# Memory_V1_0.net
KiCad netlist of a schematic drawn in EAGLE
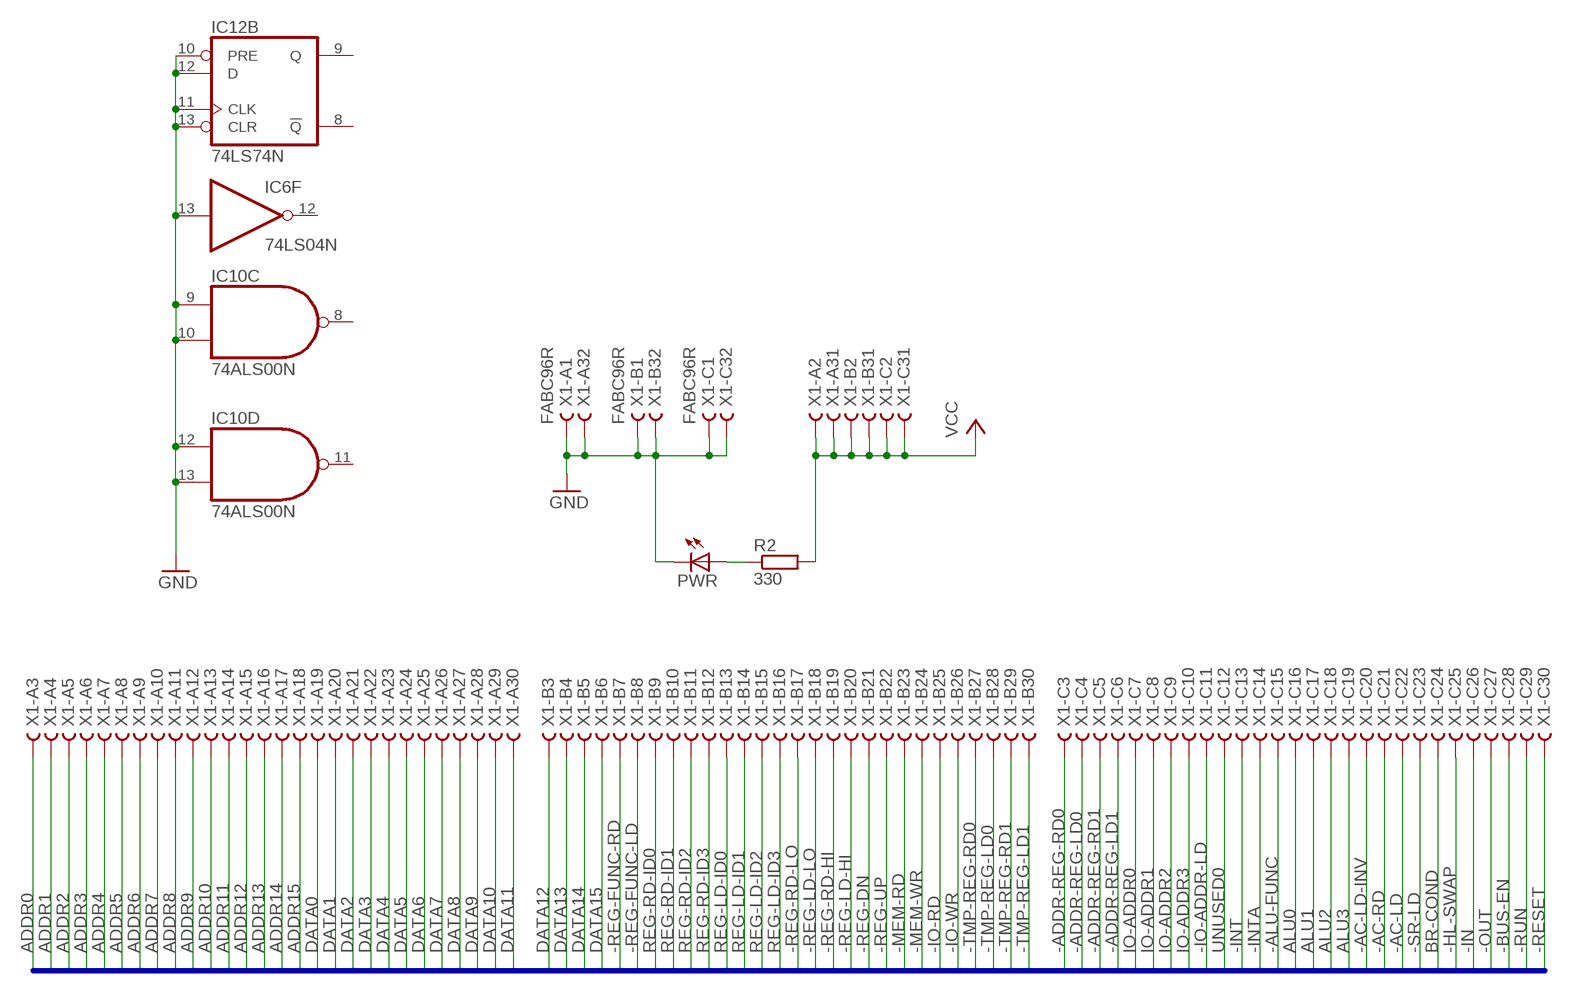
[diagram p0: schematic, sheet 1]
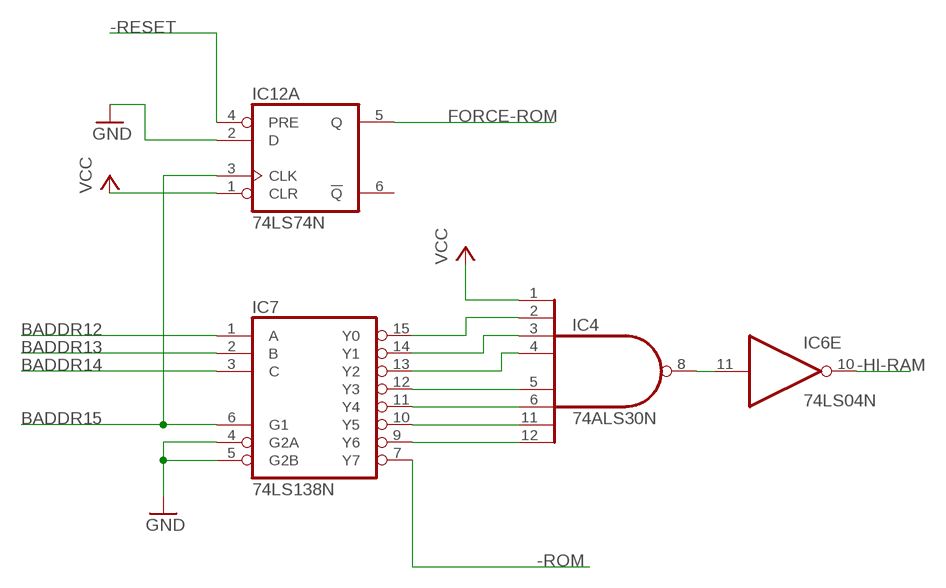
[diagram p1: schematic, sheet 2]
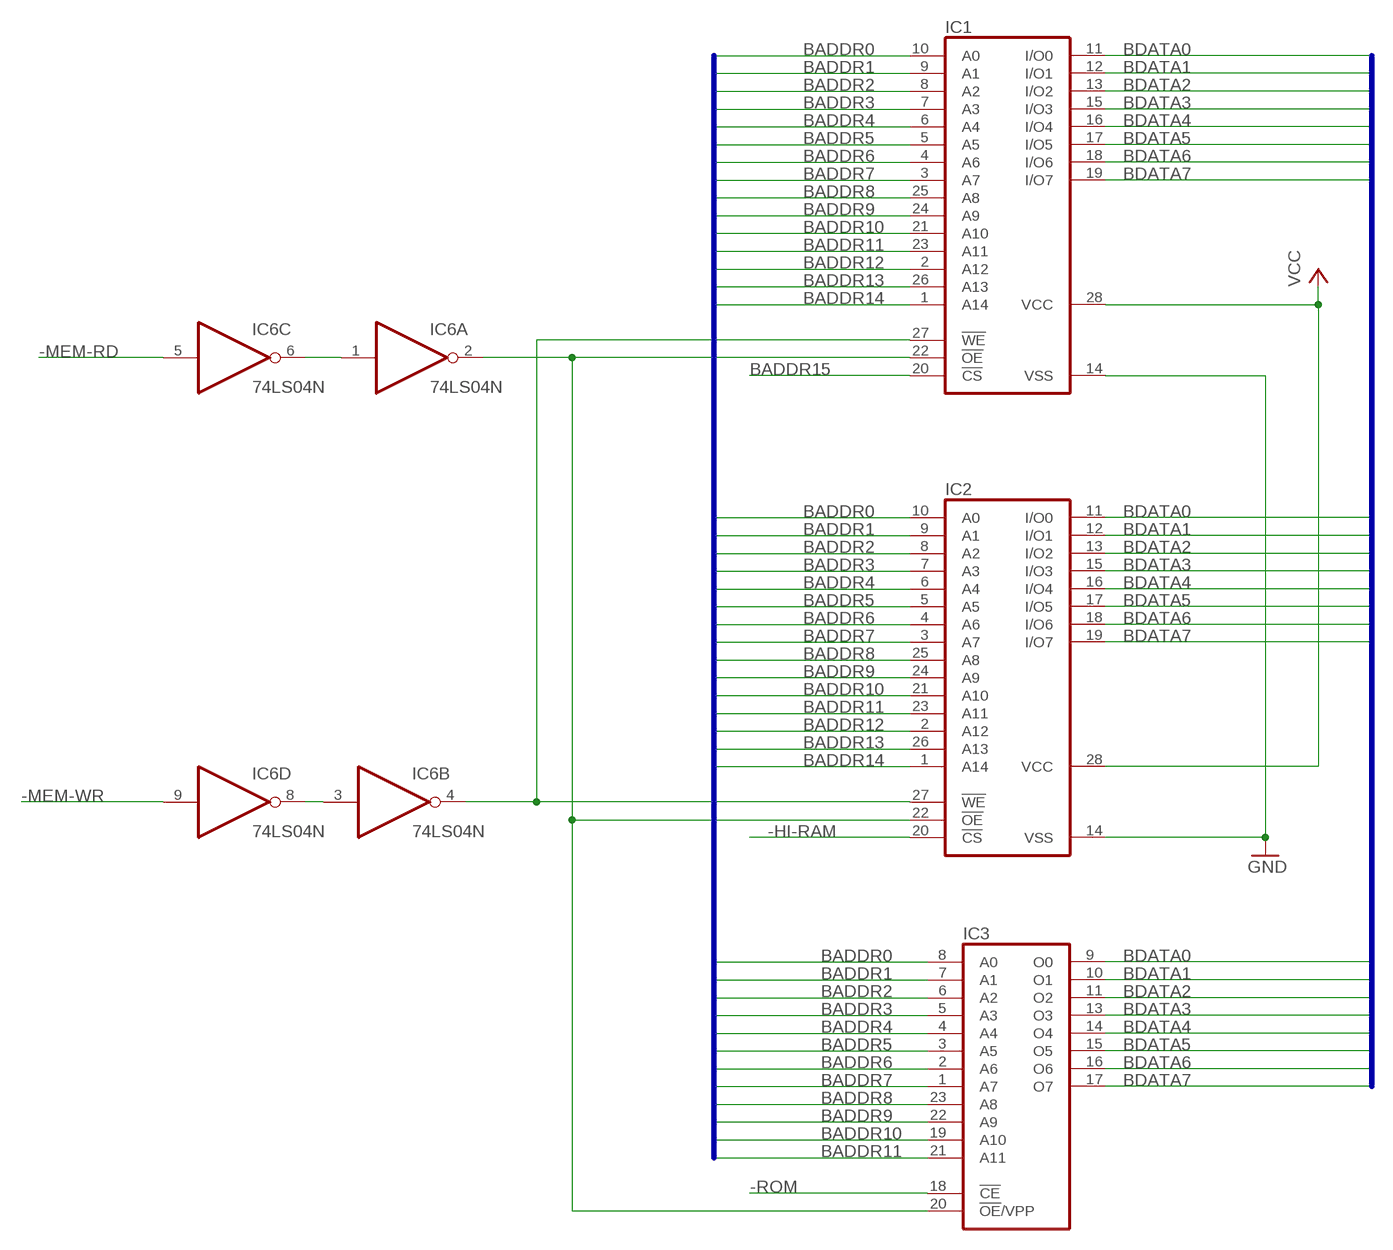
[diagram p2: schematic, sheet 3]
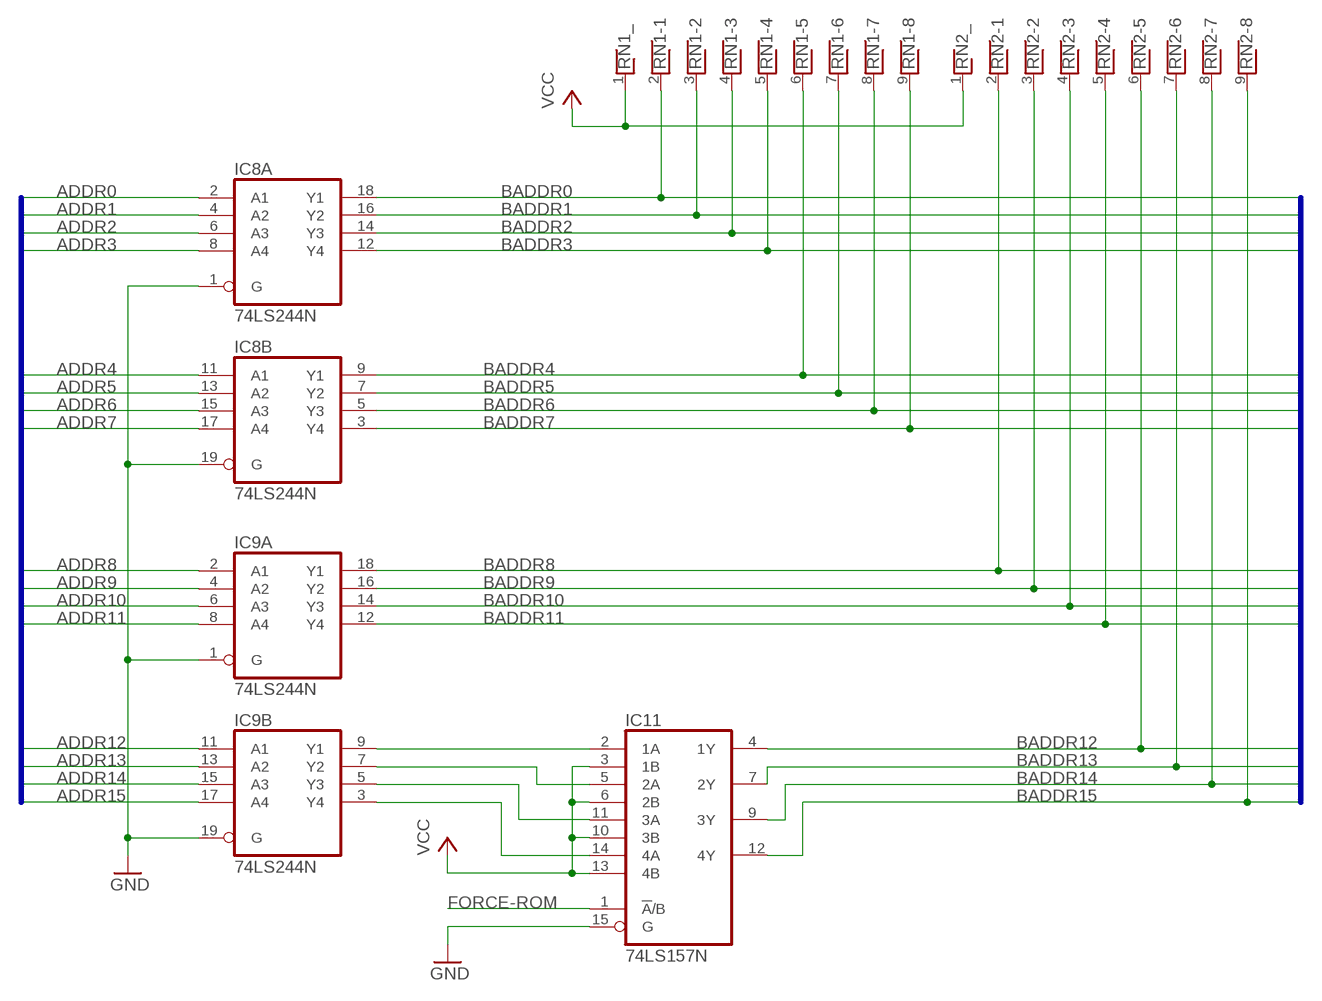
[diagram p3: schematic, sheet 4]
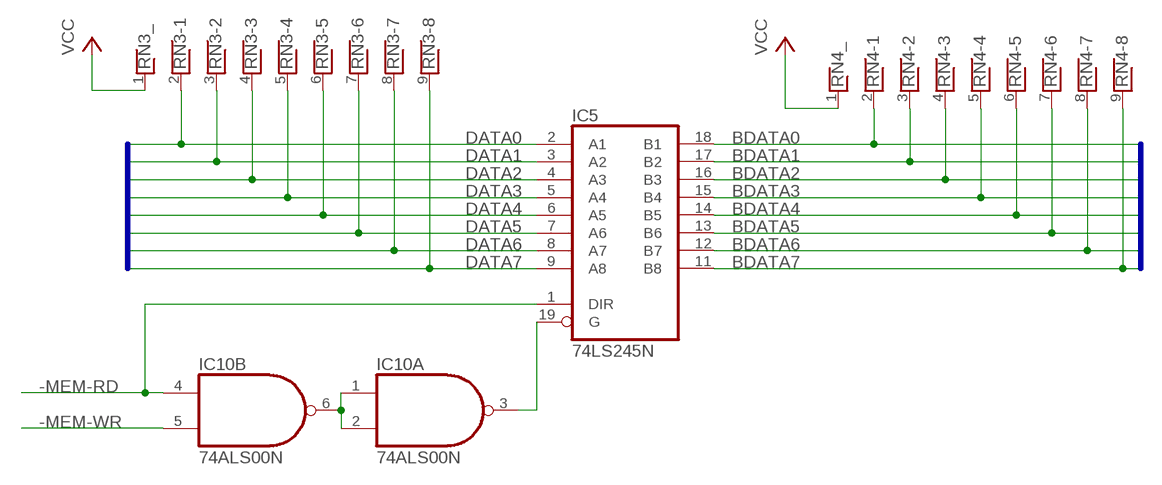
[diagram p4: schematic, sheet 5]

(export (version "E")
  (design (tool "Eeschema 10.0.6"))
  (components
    (comp (ref "IC5")
      (value "74LS245N")
      (footprint "eagle-import:DIL20")
      (libsource (lib "eagle-import") (part "74245NLS"))
    )
    (comp (ref "IC10")
      (value "74ALS00N")
      (footprint "eagle-import:DIL14")
      (libsource (lib "eagle-import") (part "7400NALS"))
    )
    (comp (ref "RN3")
      (value "RNX8")
      (footprint "eagle-import:RN-9")
      (libsource (lib "eagle-import") (part "RNX8"))
    )
    (comp (ref "RN4")
      (value "RNX8")
      (footprint "eagle-import:RN-9")
      (libsource (lib "eagle-import") (part "RNX8"))
    )
    (comp (ref "IC6")
      (value "74LS04N")
      (footprint "eagle-import:DIL14")
      (libsource (lib "eagle-import") (part "7404NLS"))
    )
    (comp (ref "IC12")
      (value "74LS74N")
      (footprint "eagle-import:DIL14")
      (libsource (lib "eagle-import") (part "7474NLS"))
    )
    (comp (ref "PWR")
      (value "LED5MM")
      (footprint "eagle-import:LED5MM")
      (libsource (lib "eagle-import") (part "LED5MM"))
    )
    (comp (ref "R2")
      (value "330")
      (footprint "eagle-import:0207_10")
      (libsource (lib "eagle-import") (part "R0207/10"))
    )
    (comp (ref "X1")
      (value "FABC96R")
      (footprint "eagle-import:FABC96R")
      (libsource (lib "eagle-import") (part "FABC96R"))
    )
    (comp (ref "IC1")
      (value "62256P")
      (footprint "eagle-import:DIL28-6")
      (libsource (lib "eagle-import") (part "62256P"))
    )
    (comp (ref "IC2")
      (value "62256P")
      (footprint "eagle-import:DIL28-6")
      (libsource (lib "eagle-import") (part "62256P"))
    )
    (comp (ref "IC3")
      (value "2732")
      (footprint "eagle-import:DIL24")
      (libsource (lib "eagle-import") (part "2732"))
    )
    (comp (ref "IC8")
      (value "74LS244N")
      (footprint "eagle-import:DIL20")
      (libsource (lib "eagle-import") (part "74xx-us_88_74244NLS"))
    )
    (comp (ref "IC9")
      (value "74LS244N")
      (footprint "eagle-import:DIL20")
      (libsource (lib "eagle-import") (part "74xx-us_88_74244NLS"))
    )
    (comp (ref "IC11")
      (value "74LS157N")
      (footprint "eagle-import:DIL16")
      (libsource (lib "eagle-import") (part "74157NLS"))
    )
    (comp (ref "RN1")
      (value "RNX8")
      (footprint "eagle-import:RN-9")
      (libsource (lib "eagle-import") (part "RNX8"))
    )
    (comp (ref "RN2")
      (value "RNX8")
      (footprint "eagle-import:RN-9")
      (libsource (lib "eagle-import") (part "RNX8"))
    )
    (comp (ref "IC4")
      (value "74ALS30N")
      (footprint "eagle-import:DIL14")
      (libsource (lib "eagle-import") (part "7430NALS"))
    )
    (comp (ref "IC7")
      (value "74LS138N")
      (footprint "eagle-import:DIL16")
      (libsource (lib "eagle-import") (part "74138NLS"))
    )
  )
  (nets
    (net (code "1") (name "-AC-LD") (class "Default")
      (node (ref "X1") (pin "C22") (pinfunction "B_C22") (pintype "passive"))
    )
    (net (code "2") (name "-AC-LD-INV") (class "Default")
      (node (ref "X1") (pin "C20") (pinfunction "B_C20") (pintype "passive"))
    )
    (net (code "3") (name "-AC-RD") (class "Default")
      (node (ref "X1") (pin "C21") (pinfunction "B_C21") (pintype "passive"))
    )
    (net (code "4") (name "-ADDR-REG-LD0") (class "Default")
      (node (ref "X1") (pin "C4") (pinfunction "B_C4") (pintype "passive"))
    )
    (net (code "5") (name "-ADDR-REG-LD1") (class "Default")
      (node (ref "X1") (pin "C6") (pinfunction "B_C6") (pintype "passive"))
    )
    (net (code "6") (name "-ADDR-REG-RD0") (class "Default")
      (node (ref "X1") (pin "C3") (pinfunction "B_C3") (pintype "passive"))
    )
    (net (code "7") (name "-ADDR-REG-RD1") (class "Default")
      (node (ref "X1") (pin "C5") (pinfunction "B_C5") (pintype "passive"))
    )
    (net (code "8") (name "-ALU-FUNC") (class "Default")
      (node (ref "X1") (pin "C15") (pinfunction "B_C15") (pintype "passive"))
    )
    (net (code "9") (name "-BUS-EN") (class "Default")
      (node (ref "X1") (pin "C28") (pinfunction "B_C28") (pintype "passive"))
    )
    (net (code "10") (name "-HI-RAM") (class "Default")
      (node (ref "IC2") (pin "20") (pinfunction "~{CS}_20") (pintype "input"))
      (node (ref "IC6") (pin "10") (pinfunction "O_10") (pintype "output"))
    )
    (net (code "11") (name "-HL-SWAP") (class "Default")
      (node (ref "X1") (pin "C25") (pinfunction "B_C25") (pintype "passive"))
    )
    (net (code "12") (name "-IN") (class "Default")
      (node (ref "X1") (pin "C26") (pinfunction "B_C26") (pintype "passive"))
    )
    (net (code "13") (name "-INT") (class "Default")
      (node (ref "X1") (pin "C13") (pinfunction "B_C13") (pintype "passive"))
    )
    (net (code "14") (name "-INTA") (class "Default")
      (node (ref "X1") (pin "C14") (pinfunction "B_C14") (pintype "passive"))
    )
    (net (code "15") (name "-IO-ADDR-LD") (class "Default")
      (node (ref "X1") (pin "C11") (pinfunction "B_C11") (pintype "passive"))
    )
    (net (code "16") (name "-IO-RD") (class "Default")
      (node (ref "X1") (pin "B25") (pinfunction "B_B25") (pintype "passive"))
    )
    (net (code "17") (name "-IO-WR") (class "Default")
      (node (ref "X1") (pin "B26") (pinfunction "B_B26") (pintype "passive"))
    )
    (net (code "18") (name "-MEM-RD") (class "Default")
      (node (ref "IC10") (pin "4") (pinfunction "I0_4") (pintype "input"))
      (node (ref "IC5") (pin "1") (pinfunction "DIR_1") (pintype "input"))
      (node (ref "IC6") (pin "5") (pinfunction "I_5") (pintype "input"))
      (node (ref "X1") (pin "B23") (pinfunction "B_B23") (pintype "passive"))
    )
    (net (code "19") (name "-MEM-WR") (class "Default")
      (node (ref "IC10") (pin "5") (pinfunction "I1_5") (pintype "input"))
      (node (ref "IC6") (pin "9") (pinfunction "I_9") (pintype "input"))
      (node (ref "X1") (pin "B24") (pinfunction "B_B24") (pintype "passive"))
    )
    (net (code "20") (name "-OUT") (class "Default")
      (node (ref "X1") (pin "C27") (pinfunction "B_C27") (pintype "passive"))
    )
    (net (code "21") (name "-REG-DN") (class "Default")
      (node (ref "X1") (pin "B21") (pinfunction "B_B21") (pintype "passive"))
    )
    (net (code "22") (name "-REG-FUNC-LD") (class "Default")
      (node (ref "X1") (pin "B8") (pinfunction "B_B8") (pintype "passive"))
    )
    (net (code "23") (name "-REG-FUNC-RD") (class "Default")
      (node (ref "X1") (pin "B7") (pinfunction "B_B7") (pintype "passive"))
    )
    (net (code "24") (name "-REG-LD-HI") (class "Default")
      (node (ref "X1") (pin "B20") (pinfunction "B_B20") (pintype "passive"))
    )
    (net (code "25") (name "-REG-LD-LO") (class "Default")
      (node (ref "X1") (pin "B18") (pinfunction "B_B18") (pintype "passive"))
    )
    (net (code "26") (name "-REG-RD-HI") (class "Default")
      (node (ref "X1") (pin "B19") (pinfunction "B_B19") (pintype "passive"))
    )
    (net (code "27") (name "-REG-RD-LO") (class "Default")
      (node (ref "X1") (pin "B17") (pinfunction "B_B17") (pintype "passive"))
    )
    (net (code "28") (name "-REG-UP") (class "Default")
      (node (ref "X1") (pin "B22") (pinfunction "B_B22") (pintype "passive"))
    )
    (net (code "29") (name "-RESET") (class "Default")
      (node (ref "IC12") (pin "4") (pinfunction "PRE_4") (pintype "input"))
      (node (ref "X1") (pin "C30") (pinfunction "B_C30") (pintype "passive"))
    )
    (net (code "30") (name "-ROM") (class "Default")
      (node (ref "IC3") (pin "18") (pinfunction "~{CE}_18") (pintype "input"))
      (node (ref "IC7") (pin "7") (pinfunction "Y7_7") (pintype "output"))
    )
    (net (code "31") (name "-RUN") (class "Default")
      (node (ref "X1") (pin "C29") (pinfunction "B_C29") (pintype "passive"))
    )
    (net (code "32") (name "-SR-LD") (class "Default")
      (node (ref "X1") (pin "C23") (pinfunction "B_C23") (pintype "passive"))
    )
    (net (code "33") (name "-TMP-REG-LD0") (class "Default")
      (node (ref "X1") (pin "B28") (pinfunction "B_B28") (pintype "passive"))
    )
    (net (code "34") (name "-TMP-REG-LD1") (class "Default")
      (node (ref "X1") (pin "B30") (pinfunction "B_B30") (pintype "passive"))
    )
    (net (code "35") (name "-TMP-REG-RD0") (class "Default")
      (node (ref "X1") (pin "B27") (pinfunction "B_B27") (pintype "passive"))
    )
    (net (code "36") (name "-TMP-REG-RD1") (class "Default")
      (node (ref "X1") (pin "B29") (pinfunction "B_B29") (pintype "passive"))
    )
    (net (code "37") (name "ADDR0") (class "Default")
      (node (ref "IC8") (pin "2") (pinfunction "A1_2") (pintype "input"))
      (node (ref "X1") (pin "A3") (pinfunction "B_A3") (pintype "passive"))
    )
    (net (code "38") (name "ADDR1") (class "Default")
      (node (ref "IC8") (pin "4") (pinfunction "A2_4") (pintype "input"))
      (node (ref "X1") (pin "A4") (pinfunction "B_A4") (pintype "passive"))
    )
    (net (code "39") (name "ADDR2") (class "Default")
      (node (ref "IC8") (pin "6") (pinfunction "A3_6") (pintype "input"))
      (node (ref "X1") (pin "A5") (pinfunction "B_A5") (pintype "passive"))
    )
    (net (code "40") (name "ADDR3") (class "Default")
      (node (ref "IC8") (pin "8") (pinfunction "A4_8") (pintype "input"))
      (node (ref "X1") (pin "A6") (pinfunction "B_A6") (pintype "passive"))
    )
    (net (code "41") (name "ADDR4") (class "Default")
      (node (ref "IC8") (pin "11") (pinfunction "A1_11") (pintype "input"))
      (node (ref "X1") (pin "A7") (pinfunction "B_A7") (pintype "passive"))
    )
    (net (code "42") (name "ADDR5") (class "Default")
      (node (ref "IC8") (pin "13") (pinfunction "A2_13") (pintype "input"))
      (node (ref "X1") (pin "A8") (pinfunction "B_A8") (pintype "passive"))
    )
    (net (code "43") (name "ADDR6") (class "Default")
      (node (ref "IC8") (pin "15") (pinfunction "A3_15") (pintype "input"))
      (node (ref "X1") (pin "A9") (pinfunction "B_A9") (pintype "passive"))
    )
    (net (code "44") (name "ADDR7") (class "Default")
      (node (ref "IC8") (pin "17") (pinfunction "A4_17") (pintype "input"))
      (node (ref "X1") (pin "A10") (pinfunction "B_A10") (pintype "passive"))
    )
    (net (code "45") (name "ADDR8") (class "Default")
      (node (ref "IC9") (pin "2") (pinfunction "A1_2") (pintype "input"))
      (node (ref "X1") (pin "A11") (pinfunction "B_A11") (pintype "passive"))
    )
    (net (code "46") (name "ADDR9") (class "Default")
      (node (ref "IC9") (pin "4") (pinfunction "A2_4") (pintype "input"))
      (node (ref "X1") (pin "A12") (pinfunction "B_A12") (pintype "passive"))
    )
    (net (code "47") (name "ADDR10") (class "Default")
      (node (ref "IC9") (pin "6") (pinfunction "A3_6") (pintype "input"))
      (node (ref "X1") (pin "A13") (pinfunction "B_A13") (pintype "passive"))
    )
    (net (code "48") (name "ADDR11") (class "Default")
      (node (ref "IC9") (pin "8") (pinfunction "A4_8") (pintype "input"))
      (node (ref "X1") (pin "A14") (pinfunction "B_A14") (pintype "passive"))
    )
    (net (code "49") (name "ADDR12") (class "Default")
      (node (ref "IC9") (pin "11") (pinfunction "A1_11") (pintype "input"))
      (node (ref "X1") (pin "A15") (pinfunction "B_A15") (pintype "passive"))
    )
    (net (code "50") (name "ADDR13") (class "Default")
      (node (ref "IC9") (pin "13") (pinfunction "A2_13") (pintype "input"))
      (node (ref "X1") (pin "A16") (pinfunction "B_A16") (pintype "passive"))
    )
    (net (code "51") (name "ADDR14") (class "Default")
      (node (ref "IC9") (pin "15") (pinfunction "A3_15") (pintype "input"))
      (node (ref "X1") (pin "A17") (pinfunction "B_A17") (pintype "passive"))
    )
    (net (code "52") (name "ADDR15") (class "Default")
      (node (ref "IC9") (pin "17") (pinfunction "A4_17") (pintype "input"))
      (node (ref "X1") (pin "A18") (pinfunction "B_A18") (pintype "passive"))
    )
    (net (code "53") (name "ALU0") (class "Default")
      (node (ref "X1") (pin "C16") (pinfunction "B_C16") (pintype "passive"))
    )
    (net (code "54") (name "ALU1") (class "Default")
      (node (ref "X1") (pin "C17") (pinfunction "B_C17") (pintype "passive"))
    )
    (net (code "55") (name "ALU2") (class "Default")
      (node (ref "X1") (pin "C18") (pinfunction "B_C18") (pintype "passive"))
    )
    (net (code "56") (name "ALU3") (class "Default")
      (node (ref "X1") (pin "C19") (pinfunction "B_C19") (pintype "passive"))
    )
    (net (code "57") (name "BADDR0") (class "Default")
      (node (ref "IC1") (pin "10") (pinfunction "A0_10") (pintype "input"))
      (node (ref "IC2") (pin "10") (pinfunction "A0_10") (pintype "input"))
      (node (ref "IC3") (pin "8") (pinfunction "A0_8") (pintype "input"))
      (node (ref "IC8") (pin "18") (pinfunction "Y1_18") (pintype "tri_state"))
      (node (ref "RN1") (pin "2") (pinfunction "1_2") (pintype "passive"))
    )
    (net (code "58") (name "BADDR1") (class "Default")
      (node (ref "IC1") (pin "9") (pinfunction "A1_9") (pintype "input"))
      (node (ref "IC2") (pin "9") (pinfunction "A1_9") (pintype "input"))
      (node (ref "IC3") (pin "7") (pinfunction "A1_7") (pintype "input"))
      (node (ref "IC8") (pin "16") (pinfunction "Y2_16") (pintype "tri_state"))
      (node (ref "RN1") (pin "3") (pinfunction "1_3") (pintype "passive"))
    )
    (net (code "59") (name "BADDR2") (class "Default")
      (node (ref "IC1") (pin "8") (pinfunction "A2_8") (pintype "input"))
      (node (ref "IC2") (pin "8") (pinfunction "A2_8") (pintype "input"))
      (node (ref "IC3") (pin "6") (pinfunction "A2_6") (pintype "input"))
      (node (ref "IC8") (pin "14") (pinfunction "Y3_14") (pintype "tri_state"))
      (node (ref "RN1") (pin "4") (pinfunction "1_4") (pintype "passive"))
    )
    (net (code "60") (name "BADDR3") (class "Default")
      (node (ref "IC1") (pin "7") (pinfunction "A3_7") (pintype "input"))
      (node (ref "IC2") (pin "7") (pinfunction "A3_7") (pintype "input"))
      (node (ref "IC3") (pin "5") (pinfunction "A3_5") (pintype "input"))
      (node (ref "IC8") (pin "12") (pinfunction "Y4_12") (pintype "tri_state"))
      (node (ref "RN1") (pin "5") (pinfunction "1_5") (pintype "passive"))
    )
    (net (code "61") (name "BADDR4") (class "Default")
      (node (ref "IC1") (pin "6") (pinfunction "A4_6") (pintype "input"))
      (node (ref "IC2") (pin "6") (pinfunction "A4_6") (pintype "input"))
      (node (ref "IC3") (pin "4") (pinfunction "A4_4") (pintype "input"))
      (node (ref "IC8") (pin "9") (pinfunction "Y1_9") (pintype "tri_state"))
      (node (ref "RN1") (pin "6") (pinfunction "1_6") (pintype "passive"))
    )
    (net (code "62") (name "BADDR5") (class "Default")
      (node (ref "IC1") (pin "5") (pinfunction "A5_5") (pintype "input"))
      (node (ref "IC2") (pin "5") (pinfunction "A5_5") (pintype "input"))
      (node (ref "IC3") (pin "3") (pinfunction "A5_3") (pintype "input"))
      (node (ref "IC8") (pin "7") (pinfunction "Y2_7") (pintype "tri_state"))
      (node (ref "RN1") (pin "7") (pinfunction "1_7") (pintype "passive"))
    )
    (net (code "63") (name "BADDR6") (class "Default")
      (node (ref "IC1") (pin "4") (pinfunction "A6_4") (pintype "input"))
      (node (ref "IC2") (pin "4") (pinfunction "A6_4") (pintype "input"))
      (node (ref "IC3") (pin "2") (pinfunction "A6_2") (pintype "input"))
      (node (ref "IC8") (pin "5") (pinfunction "Y3_5") (pintype "tri_state"))
      (node (ref "RN1") (pin "8") (pinfunction "1_8") (pintype "passive"))
    )
    (net (code "64") (name "BADDR7") (class "Default")
      (node (ref "IC1") (pin "3") (pinfunction "A7_3") (pintype "input"))
      (node (ref "IC2") (pin "3") (pinfunction "A7_3") (pintype "input"))
      (node (ref "IC3") (pin "1") (pinfunction "A7_1") (pintype "input"))
      (node (ref "IC8") (pin "3") (pinfunction "Y4_3") (pintype "tri_state"))
      (node (ref "RN1") (pin "9") (pinfunction "1_9") (pintype "passive"))
    )
    (net (code "65") (name "BADDR8") (class "Default")
      (node (ref "IC1") (pin "25") (pinfunction "A8_25") (pintype "input"))
      (node (ref "IC2") (pin "25") (pinfunction "A8_25") (pintype "input"))
      (node (ref "IC3") (pin "23") (pinfunction "A8_23") (pintype "input"))
      (node (ref "IC9") (pin "18") (pinfunction "Y1_18") (pintype "tri_state"))
      (node (ref "RN2") (pin "2") (pinfunction "1_2") (pintype "passive"))
    )
    (net (code "66") (name "BADDR9") (class "Default")
      (node (ref "IC1") (pin "24") (pinfunction "A9_24") (pintype "input"))
      (node (ref "IC2") (pin "24") (pinfunction "A9_24") (pintype "input"))
      (node (ref "IC3") (pin "22") (pinfunction "A9_22") (pintype "input"))
      (node (ref "IC9") (pin "16") (pinfunction "Y2_16") (pintype "tri_state"))
      (node (ref "RN2") (pin "3") (pinfunction "1_3") (pintype "passive"))
    )
    (net (code "67") (name "BADDR10") (class "Default")
      (node (ref "IC1") (pin "21") (pinfunction "A10_21") (pintype "input"))
      (node (ref "IC2") (pin "21") (pinfunction "A10_21") (pintype "input"))
      (node (ref "IC3") (pin "19") (pinfunction "A10_19") (pintype "input"))
      (node (ref "IC9") (pin "14") (pinfunction "Y3_14") (pintype "tri_state"))
      (node (ref "RN2") (pin "4") (pinfunction "1_4") (pintype "passive"))
    )
    (net (code "68") (name "BADDR11") (class "Default")
      (node (ref "IC1") (pin "23") (pinfunction "A11_23") (pintype "input"))
      (node (ref "IC2") (pin "23") (pinfunction "A11_23") (pintype "input"))
      (node (ref "IC3") (pin "21") (pinfunction "A11_21") (pintype "input"))
      (node (ref "IC9") (pin "12") (pinfunction "Y4_12") (pintype "tri_state"))
      (node (ref "RN2") (pin "5") (pinfunction "1_5") (pintype "passive"))
    )
    (net (code "69") (name "BADDR12") (class "Default")
      (node (ref "IC1") (pin "2") (pinfunction "A12_2") (pintype "input"))
      (node (ref "IC11") (pin "4") (pinfunction "1Y_4") (pintype "output"))
      (node (ref "IC2") (pin "2") (pinfunction "A12_2") (pintype "input"))
      (node (ref "IC7") (pin "1") (pinfunction "A_1") (pintype "input"))
      (node (ref "RN2") (pin "6") (pinfunction "1_6") (pintype "passive"))
    )
    (net (code "70") (name "BADDR13") (class "Default")
      (node (ref "IC1") (pin "26") (pinfunction "A13_26") (pintype "input"))
      (node (ref "IC11") (pin "7") (pinfunction "2Y_7") (pintype "output"))
      (node (ref "IC2") (pin "26") (pinfunction "A13_26") (pintype "input"))
      (node (ref "IC7") (pin "2") (pinfunction "B_2") (pintype "input"))
      (node (ref "RN2") (pin "7") (pinfunction "1_7") (pintype "passive"))
    )
    (net (code "71") (name "BADDR14") (class "Default")
      (node (ref "IC1") (pin "1") (pinfunction "A14_1") (pintype "input"))
      (node (ref "IC11") (pin "9") (pinfunction "3Y_9") (pintype "output"))
      (node (ref "IC2") (pin "1") (pinfunction "A14_1") (pintype "input"))
      (node (ref "IC7") (pin "3") (pinfunction "C_3") (pintype "input"))
      (node (ref "RN2") (pin "8") (pinfunction "1_8") (pintype "passive"))
    )
    (net (code "72") (name "BADDR15") (class "Default")
      (node (ref "IC1") (pin "20") (pinfunction "~{CS}_20") (pintype "input"))
      (node (ref "IC11") (pin "12") (pinfunction "4Y_12") (pintype "output"))
      (node (ref "IC12") (pin "3") (pinfunction "CLK_3") (pintype "input"))
      (node (ref "IC7") (pin "6") (pinfunction "G1_6") (pintype "input"))
      (node (ref "RN2") (pin "9") (pinfunction "1_9") (pintype "passive"))
    )
    (net (code "73") (name "BDATA0") (class "Default")
      (node (ref "IC1") (pin "11") (pinfunction "I/O0_11") (pintype "bidirectional"))
      (node (ref "IC2") (pin "11") (pinfunction "I/O0_11") (pintype "bidirectional"))
      (node (ref "IC3") (pin "9") (pinfunction "O0_9") (pintype "tri_state"))
      (node (ref "IC5") (pin "18") (pinfunction "B1_18") (pintype "bidirectional"))
      (node (ref "RN4") (pin "2") (pinfunction "1_2") (pintype "passive"))
    )
    (net (code "74") (name "BDATA1") (class "Default")
      (node (ref "IC1") (pin "12") (pinfunction "I/O1_12") (pintype "bidirectional"))
      (node (ref "IC2") (pin "12") (pinfunction "I/O1_12") (pintype "bidirectional"))
      (node (ref "IC3") (pin "10") (pinfunction "O1_10") (pintype "tri_state"))
      (node (ref "IC5") (pin "17") (pinfunction "B2_17") (pintype "bidirectional"))
      (node (ref "RN4") (pin "3") (pinfunction "1_3") (pintype "passive"))
    )
    (net (code "75") (name "BDATA2") (class "Default")
      (node (ref "IC1") (pin "13") (pinfunction "I/O2_13") (pintype "bidirectional"))
      (node (ref "IC2") (pin "13") (pinfunction "I/O2_13") (pintype "bidirectional"))
      (node (ref "IC3") (pin "11") (pinfunction "O2_11") (pintype "tri_state"))
      (node (ref "IC5") (pin "16") (pinfunction "B3_16") (pintype "bidirectional"))
      (node (ref "RN4") (pin "4") (pinfunction "1_4") (pintype "passive"))
    )
    (net (code "76") (name "BDATA3") (class "Default")
      (node (ref "IC1") (pin "15") (pinfunction "I/O3_15") (pintype "bidirectional"))
      (node (ref "IC2") (pin "15") (pinfunction "I/O3_15") (pintype "bidirectional"))
      (node (ref "IC3") (pin "13") (pinfunction "O3_13") (pintype "tri_state"))
      (node (ref "IC5") (pin "15") (pinfunction "B4_15") (pintype "bidirectional"))
      (node (ref "RN4") (pin "5") (pinfunction "1_5") (pintype "passive"))
    )
    (net (code "77") (name "BDATA4") (class "Default")
      (node (ref "IC1") (pin "16") (pinfunction "I/O4_16") (pintype "bidirectional"))
      (node (ref "IC2") (pin "16") (pinfunction "I/O4_16") (pintype "bidirectional"))
      (node (ref "IC3") (pin "14") (pinfunction "O4_14") (pintype "tri_state"))
      (node (ref "IC5") (pin "14") (pinfunction "B5_14") (pintype "bidirectional"))
      (node (ref "RN4") (pin "6") (pinfunction "1_6") (pintype "passive"))
    )
    (net (code "78") (name "BDATA5") (class "Default")
      (node (ref "IC1") (pin "17") (pinfunction "I/O5_17") (pintype "bidirectional"))
      (node (ref "IC2") (pin "17") (pinfunction "I/O5_17") (pintype "bidirectional"))
      (node (ref "IC3") (pin "15") (pinfunction "O5_15") (pintype "tri_state"))
      (node (ref "IC5") (pin "13") (pinfunction "B6_13") (pintype "bidirectional"))
      (node (ref "RN4") (pin "7") (pinfunction "1_7") (pintype "passive"))
    )
    (net (code "79") (name "BDATA6") (class "Default")
      (node (ref "IC1") (pin "18") (pinfunction "I/O6_18") (pintype "bidirectional"))
      (node (ref "IC2") (pin "18") (pinfunction "I/O6_18") (pintype "bidirectional"))
      (node (ref "IC3") (pin "16") (pinfunction "O6_16") (pintype "tri_state"))
      (node (ref "IC5") (pin "12") (pinfunction "B7_12") (pintype "bidirectional"))
      (node (ref "RN4") (pin "8") (pinfunction "1_8") (pintype "passive"))
    )
    (net (code "80") (name "BDATA7") (class "Default")
      (node (ref "IC1") (pin "19") (pinfunction "I/O7_19") (pintype "bidirectional"))
      (node (ref "IC2") (pin "19") (pinfunction "I/O7_19") (pintype "bidirectional"))
      (node (ref "IC3") (pin "17") (pinfunction "O7_17") (pintype "tri_state"))
      (node (ref "IC5") (pin "11") (pinfunction "B8_11") (pintype "bidirectional"))
      (node (ref "RN4") (pin "9") (pinfunction "1_9") (pintype "passive"))
    )
    (net (code "81") (name "BR-COND") (class "Default")
      (node (ref "X1") (pin "C24") (pinfunction "B_C24") (pintype "passive"))
    )
    (net (code "82") (name "DATA0") (class "Default")
      (node (ref "IC5") (pin "2") (pinfunction "A1_2") (pintype "bidirectional"))
      (node (ref "RN3") (pin "2") (pinfunction "1_2") (pintype "passive"))
      (node (ref "X1") (pin "A19") (pinfunction "B_A19") (pintype "passive"))
    )
    (net (code "83") (name "DATA1") (class "Default")
      (node (ref "IC5") (pin "3") (pinfunction "A2_3") (pintype "bidirectional"))
      (node (ref "RN3") (pin "3") (pinfunction "1_3") (pintype "passive"))
      (node (ref "X1") (pin "A20") (pinfunction "B_A20") (pintype "passive"))
    )
    (net (code "84") (name "DATA2") (class "Default")
      (node (ref "IC5") (pin "4") (pinfunction "A3_4") (pintype "bidirectional"))
      (node (ref "RN3") (pin "4") (pinfunction "1_4") (pintype "passive"))
      (node (ref "X1") (pin "A21") (pinfunction "B_A21") (pintype "passive"))
    )
    (net (code "85") (name "DATA3") (class "Default")
      (node (ref "IC5") (pin "5") (pinfunction "A4_5") (pintype "bidirectional"))
      (node (ref "RN3") (pin "5") (pinfunction "1_5") (pintype "passive"))
      (node (ref "X1") (pin "A22") (pinfunction "B_A22") (pintype "passive"))
    )
    (net (code "86") (name "DATA4") (class "Default")
      (node (ref "IC5") (pin "6") (pinfunction "A5_6") (pintype "bidirectional"))
      (node (ref "RN3") (pin "6") (pinfunction "1_6") (pintype "passive"))
      (node (ref "X1") (pin "A23") (pinfunction "B_A23") (pintype "passive"))
    )
    (net (code "87") (name "DATA5") (class "Default")
      (node (ref "IC5") (pin "7") (pinfunction "A6_7") (pintype "bidirectional"))
      (node (ref "RN3") (pin "7") (pinfunction "1_7") (pintype "passive"))
      (node (ref "X1") (pin "A24") (pinfunction "B_A24") (pintype "passive"))
    )
    (net (code "88") (name "DATA6") (class "Default")
      (node (ref "IC5") (pin "8") (pinfunction "A7_8") (pintype "bidirectional"))
      (node (ref "RN3") (pin "8") (pinfunction "1_8") (pintype "passive"))
      (node (ref "X1") (pin "A25") (pinfunction "B_A25") (pintype "passive"))
    )
    (net (code "89") (name "DATA7") (class "Default")
      (node (ref "IC5") (pin "9") (pinfunction "A8_9") (pintype "bidirectional"))
      (node (ref "RN3") (pin "9") (pinfunction "1_9") (pintype "passive"))
      (node (ref "X1") (pin "A26") (pinfunction "B_A26") (pintype "passive"))
    )
    (net (code "90") (name "DATA8") (class "Default")
      (node (ref "X1") (pin "A27") (pinfunction "B_A27") (pintype "passive"))
    )
    (net (code "91") (name "DATA9") (class "Default")
      (node (ref "X1") (pin "A28") (pinfunction "B_A28") (pintype "passive"))
    )
    (net (code "92") (name "DATA10") (class "Default")
      (node (ref "X1") (pin "A29") (pinfunction "B_A29") (pintype "passive"))
    )
    (net (code "93") (name "DATA11") (class "Default")
      (node (ref "X1") (pin "A30") (pinfunction "B_A30") (pintype "passive"))
    )
    (net (code "94") (name "DATA12") (class "Default")
      (node (ref "X1") (pin "B3") (pinfunction "B_B3") (pintype "passive"))
    )
    (net (code "95") (name "DATA13") (class "Default")
      (node (ref "X1") (pin "B4") (pinfunction "B_B4") (pintype "passive"))
    )
    (net (code "96") (name "DATA14") (class "Default")
      (node (ref "X1") (pin "B5") (pinfunction "B_B5") (pintype "passive"))
    )
    (net (code "97") (name "DATA15") (class "Default")
      (node (ref "X1") (pin "B6") (pinfunction "B_B6") (pintype "passive"))
    )
    (net (code "98") (name "FORCE-ROM") (class "Default")
      (node (ref "IC11") (pin "1") (pinfunction "~{A}/B_1") (pintype "input"))
      (node (ref "IC12") (pin "5") (pinfunction "Q_5") (pintype "output"))
    )
    (net (code "99") (name "GND") (class "Default")
      (node (ref "IC1") (pin "14") (pinfunction "VSS_14") (pintype "power_in"))
      (node (ref "IC10") (pin "10") (pinfunction "I1_10") (pintype "input"))
      (node (ref "IC10") (pin "12") (pinfunction "I0_12") (pintype "input"))
      (node (ref "IC10") (pin "13") (pinfunction "I1_13") (pintype "input"))
      (node (ref "IC10") (pin "9") (pinfunction "I0_9") (pintype "input"))
      (node (ref "IC11") (pin "15") (pinfunction "G_15") (pintype "input"))
      (node (ref "IC12") (pin "10") (pinfunction "PRE_10") (pintype "input"))
      (node (ref "IC12") (pin "11") (pinfunction "CLK_11") (pintype "input"))
      (node (ref "IC12") (pin "12") (pinfunction "D_12") (pintype "input"))
      (node (ref "IC12") (pin "13") (pinfunction "CLR_13") (pintype "input"))
      (node (ref "IC12") (pin "2") (pinfunction "D_2") (pintype "input"))
      (node (ref "IC2") (pin "14") (pinfunction "VSS_14") (pintype "power_in"))
      (node (ref "IC6") (pin "13") (pinfunction "I_13") (pintype "input"))
      (node (ref "IC7") (pin "4") (pinfunction "G2A_4") (pintype "input"))
      (node (ref "IC7") (pin "5") (pinfunction "G2B_5") (pintype "input"))
      (node (ref "IC8") (pin "1") (pinfunction "G_1") (pintype "input"))
      (node (ref "IC8") (pin "19") (pinfunction "G_19") (pintype "input"))
      (node (ref "IC9") (pin "1") (pinfunction "G_1") (pintype "input"))
      (node (ref "IC9") (pin "19") (pinfunction "G_19") (pintype "input"))
      (node (ref "PWR") (pin "K") (pinfunction "C_K") (pintype "passive"))
      (node (ref "X1") (pin "A1") (pinfunction "B_A1") (pintype "passive"))
      (node (ref "X1") (pin "A32") (pinfunction "B_A32") (pintype "passive"))
      (node (ref "X1") (pin "B1") (pinfunction "B_B1") (pintype "passive"))
      (node (ref "X1") (pin "B32") (pinfunction "B_B32") (pintype "passive"))
      (node (ref "X1") (pin "C1") (pinfunction "B_C1") (pintype "passive"))
      (node (ref "X1") (pin "C32") (pinfunction "B_C32") (pintype "passive"))
    )
    (net (code "100") (name "IO-ADDR0") (class "Default")
      (node (ref "X1") (pin "C7") (pinfunction "B_C7") (pintype "passive"))
    )
    (net (code "101") (name "IO-ADDR1") (class "Default")
      (node (ref "X1") (pin "C8") (pinfunction "B_C8") (pintype "passive"))
    )
    (net (code "102") (name "IO-ADDR2") (class "Default")
      (node (ref "X1") (pin "C9") (pinfunction "B_C9") (pintype "passive"))
    )
    (net (code "103") (name "IO-ADDR3") (class "Default")
      (node (ref "X1") (pin "C10") (pinfunction "B_C10") (pintype "passive"))
    )
    (net (code "104") (name "Net-(IC1-~{OE})") (class "Default")
      (node (ref "IC1") (pin "22") (pinfunction "~{OE}_22") (pintype "input"))
      (node (ref "IC2") (pin "22") (pinfunction "~{OE}_22") (pintype "input"))
      (node (ref "IC3") (pin "20") (pinfunction "~{OE}/VPP_20") (pintype "input"))
      (node (ref "IC6") (pin "2") (pinfunction "O_2") (pintype "output"))
    )
    (net (code "105") (name "Net-(IC1-~{WE})") (class "Default")
      (node (ref "IC1") (pin "27") (pinfunction "~{WE}_27") (pintype "input"))
      (node (ref "IC2") (pin "27") (pinfunction "~{WE}_27") (pintype "input"))
      (node (ref "IC6") (pin "4") (pinfunction "O_4") (pintype "output"))
    )
    (net (code "106") (name "Net-(IC4A-I1)") (class "Default")
      (node (ref "IC4") (pin "2") (pinfunction "I1_2") (pintype "input"))
      (node (ref "IC7") (pin "15") (pinfunction "Y0_15") (pintype "output"))
    )
    (net (code "107") (name "Net-(IC4A-I2)") (class "Default")
      (node (ref "IC4") (pin "3") (pinfunction "I2_3") (pintype "input"))
      (node (ref "IC7") (pin "14") (pinfunction "Y1_14") (pintype "output"))
    )
    (net (code "108") (name "Net-(IC4A-I3)") (class "Default")
      (node (ref "IC4") (pin "4") (pinfunction "I3_4") (pintype "input"))
      (node (ref "IC7") (pin "13") (pinfunction "Y2_13") (pintype "output"))
    )
    (net (code "109") (name "Net-(IC4A-I4)") (class "Default")
      (node (ref "IC4") (pin "5") (pinfunction "I4_5") (pintype "input"))
      (node (ref "IC7") (pin "12") (pinfunction "Y3_12") (pintype "output"))
    )
    (net (code "110") (name "Net-(IC4A-I5)") (class "Default")
      (node (ref "IC4") (pin "6") (pinfunction "I5_6") (pintype "input"))
      (node (ref "IC7") (pin "11") (pinfunction "Y4_11") (pintype "output"))
    )
    (net (code "111") (name "Net-(IC4A-I6)") (class "Default")
      (node (ref "IC4") (pin "11") (pinfunction "I6_11") (pintype "input"))
      (node (ref "IC7") (pin "10") (pinfunction "Y5_10") (pintype "output"))
    )
    (net (code "112") (name "Net-(IC4A-I7)") (class "Default")
      (node (ref "IC4") (pin "12") (pinfunction "I7_12") (pintype "input"))
      (node (ref "IC7") (pin "9") (pinfunction "Y6_9") (pintype "output"))
    )
    (net (code "113") (name "Net-(IC4A-O)") (class "Default")
      (node (ref "IC4") (pin "8") (pinfunction "O_8") (pintype "output"))
      (node (ref "IC6") (pin "11") (pinfunction "I_11") (pintype "input"))
    )
    (net (code "114") (name "Net-(IC6A-I)") (class "Default")
      (node (ref "IC6") (pin "1") (pinfunction "I_1") (pintype "input"))
      (node (ref "IC6") (pin "6") (pinfunction "O_6") (pintype "output"))
    )
    (net (code "115") (name "Net-(IC6B-I)") (class "Default")
      (node (ref "IC6") (pin "3") (pinfunction "I_3") (pintype "input"))
      (node (ref "IC6") (pin "8") (pinfunction "O_8") (pintype "output"))
    )
    (net (code "116") (name "Net-(IC10A-I0)") (class "Default")
      (node (ref "IC10") (pin "1") (pinfunction "I0_1") (pintype "input"))
      (node (ref "IC10") (pin "2") (pinfunction "I1_2") (pintype "input"))
      (node (ref "IC10") (pin "6") (pinfunction "O_6") (pintype "output"))
    )
    (net (code "117") (name "Net-(IC10A-O)") (class "Default")
      (node (ref "IC10") (pin "3") (pinfunction "O_3") (pintype "output"))
      (node (ref "IC5") (pin "19") (pinfunction "G_19") (pintype "input"))
    )
    (net (code "118") (name "Net-(IC11A-1A)") (class "Default")
      (node (ref "IC11") (pin "2") (pinfunction "1A_2") (pintype "input"))
      (node (ref "IC9") (pin "9") (pinfunction "Y1_9") (pintype "tri_state"))
    )
    (net (code "119") (name "Net-(IC11A-2A)") (class "Default")
      (node (ref "IC11") (pin "5") (pinfunction "2A_5") (pintype "input"))
      (node (ref "IC9") (pin "7") (pinfunction "Y2_7") (pintype "tri_state"))
    )
    (net (code "120") (name "Net-(IC11A-3A)") (class "Default")
      (node (ref "IC11") (pin "11") (pinfunction "3A_11") (pintype "input"))
      (node (ref "IC9") (pin "5") (pinfunction "Y3_5") (pintype "tri_state"))
    )
    (net (code "121") (name "Net-(IC11A-4A)") (class "Default")
      (node (ref "IC11") (pin "14") (pinfunction "4A_14") (pintype "input"))
      (node (ref "IC9") (pin "3") (pinfunction "Y4_3") (pintype "tri_state"))
    )
    (net (code "122") (name "Net-(PWR-PadA)") (class "Default")
      (node (ref "PWR") (pin "A") (pinfunction "A_A") (pintype "passive"))
      (node (ref "R2") (pin "1") (pinfunction "1_1") (pintype "passive"))
    )
    (net (code "123") (name "REG-LD-ID0") (class "Default")
      (node (ref "X1") (pin "B13") (pinfunction "B_B13") (pintype "passive"))
    )
    (net (code "124") (name "REG-LD-ID1") (class "Default")
      (node (ref "X1") (pin "B14") (pinfunction "B_B14") (pintype "passive"))
    )
    (net (code "125") (name "REG-LD-ID2") (class "Default")
      (node (ref "X1") (pin "B15") (pinfunction "B_B15") (pintype "passive"))
    )
    (net (code "126") (name "REG-LD-ID3") (class "Default")
      (node (ref "X1") (pin "B16") (pinfunction "B_B16") (pintype "passive"))
    )
    (net (code "127") (name "REG-RD-ID0") (class "Default")
      (node (ref "X1") (pin "B9") (pinfunction "B_B9") (pintype "passive"))
    )
    (net (code "128") (name "REG-RD-ID1") (class "Default")
      (node (ref "X1") (pin "B10") (pinfunction "B_B10") (pintype "passive"))
    )
    (net (code "129") (name "REG-RD-ID2") (class "Default")
      (node (ref "X1") (pin "B11") (pinfunction "B_B11") (pintype "passive"))
    )
    (net (code "130") (name "REG-RD-ID3") (class "Default")
      (node (ref "X1") (pin "B12") (pinfunction "B_B12") (pintype "passive"))
    )
    (net (code "131") (name "UNUSED0") (class "Default")
      (node (ref "X1") (pin "C12") (pinfunction "B_C12") (pintype "passive"))
    )
    (net (code "132") (name "VCC") (class "Default")
      (node (ref "IC1") (pin "28") (pinfunction "VCC_28") (pintype "power_in"))
      (node (ref "IC11") (pin "10") (pinfunction "3B_10") (pintype "input"))
      (node (ref "IC11") (pin "13") (pinfunction "4B_13") (pintype "input"))
      (node (ref "IC11") (pin "3") (pinfunction "1B_3") (pintype "input"))
      (node (ref "IC11") (pin "6") (pinfunction "2B_6") (pintype "input"))
      (node (ref "IC12") (pin "1") (pinfunction "CLR_1") (pintype "input"))
      (node (ref "IC2") (pin "28") (pinfunction "VCC_28") (pintype "power_in"))
      (node (ref "IC4") (pin "1") (pinfunction "I0_1") (pintype "input"))
      (node (ref "R2") (pin "2") (pinfunction "2_2") (pintype "passive"))
      (node (ref "RN1") (pin "1") (pinfunction "1_1") (pintype "passive"))
      (node (ref "RN2") (pin "1") (pinfunction "1_1") (pintype "passive"))
      (node (ref "RN3") (pin "1") (pinfunction "1_1") (pintype "passive"))
      (node (ref "RN4") (pin "1") (pinfunction "1_1") (pintype "passive"))
      (node (ref "X1") (pin "A2") (pinfunction "B_A2") (pintype "passive"))
      (node (ref "X1") (pin "A31") (pinfunction "B_A31") (pintype "passive"))
      (node (ref "X1") (pin "B2") (pinfunction "B_B2") (pintype "passive"))
      (node (ref "X1") (pin "B31") (pinfunction "B_B31") (pintype "passive"))
      (node (ref "X1") (pin "C2") (pinfunction "B_C2") (pintype "passive"))
      (node (ref "X1") (pin "C31") (pinfunction "B_C31") (pintype "passive"))
    )
    (net (code "133") (name "unconnected-(IC6F-O-Pad12)") (class "Default")
      (node (ref "IC6") (pin "12") (pinfunction "O_12") (pintype "output"))
    )
    (net (code "134") (name "unconnected-(IC10C-O-Pad8)") (class "Default")
      (node (ref "IC10") (pin "8") (pinfunction "O_8") (pintype "output"))
    )
    (net (code "135") (name "unconnected-(IC10D-O-Pad11)") (class "Default")
      (node (ref "IC10") (pin "11") (pinfunction "O_11") (pintype "output"))
    )
    (net (code "136") (name "unconnected-(IC12A-~{Q}-Pad6)") (class "Default")
      (node (ref "IC12") (pin "6") (pinfunction "~{Q}_6") (pintype "output"))
    )
    (net (code "137") (name "unconnected-(IC12B-Q-Pad9)") (class "Default")
      (node (ref "IC12") (pin "9") (pinfunction "Q_9") (pintype "output"))
    )
    (net (code "138") (name "unconnected-(IC12B-~{Q}-Pad8)") (class "Default")
      (node (ref "IC12") (pin "8") (pinfunction "~{Q}_8") (pintype "output"))
    )
  )
)
